# LTC6804-2_8S_TR.net
KiCad netlist of a schematic drawn in Altium Designer
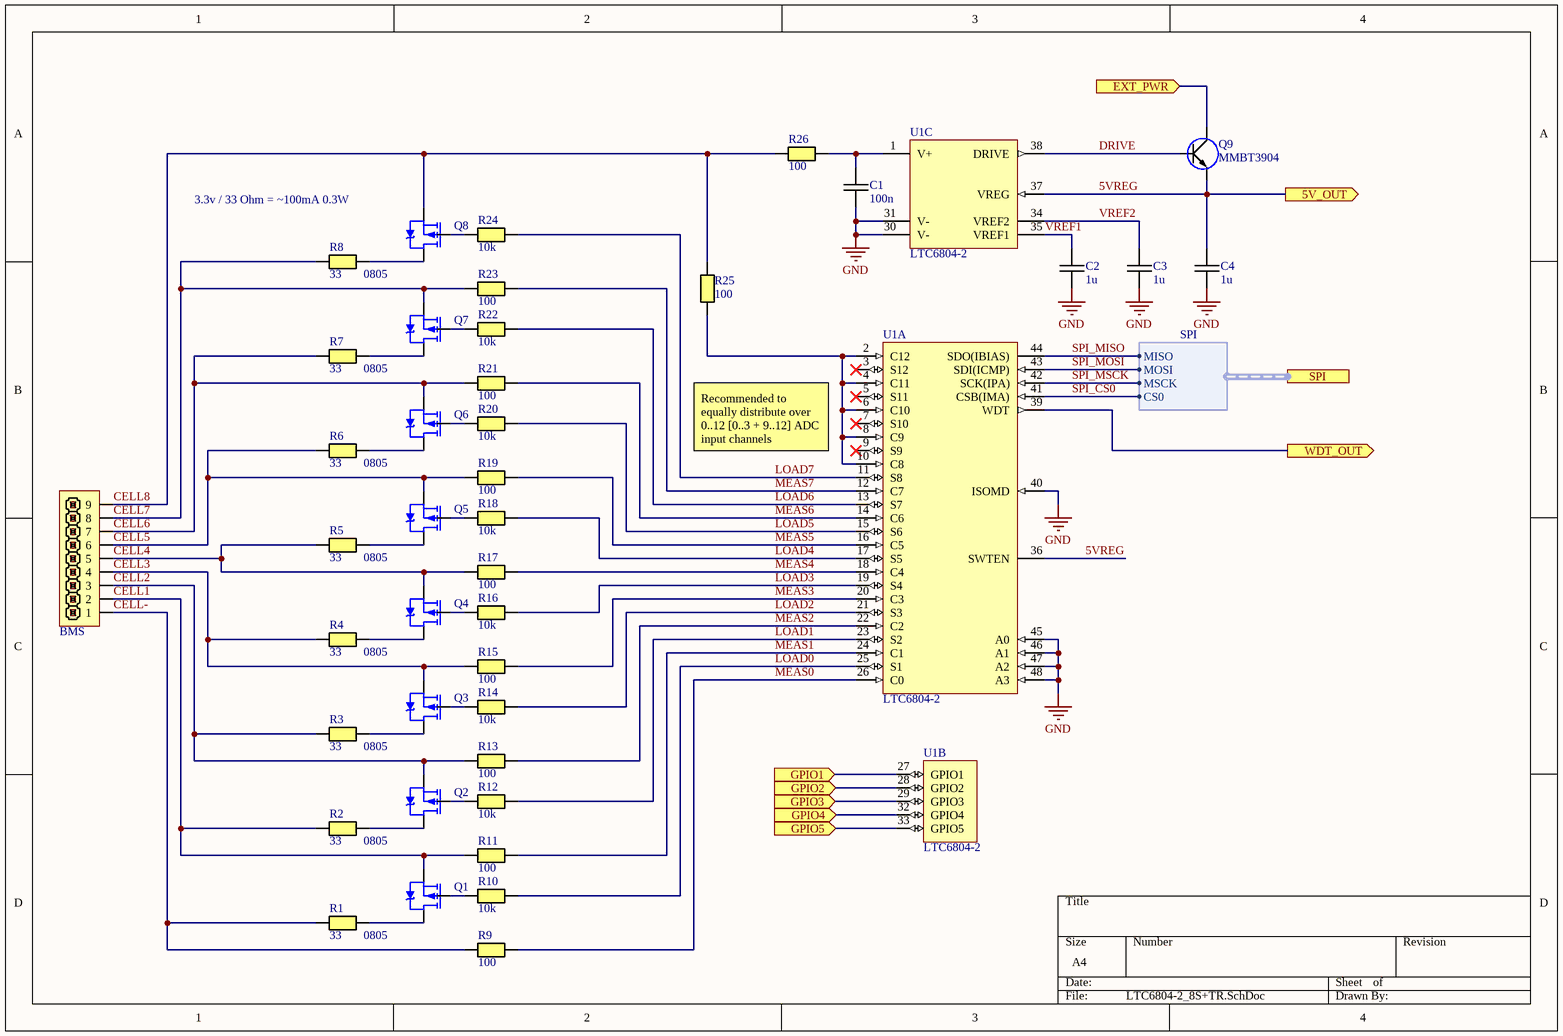
[diagram p0: LTC6804-2_8S+TR.SchDoc]

(export (version "E")
  (design (tool "Eeschema 10.0.6"))
  (components
    (comp (ref "BMS")
      (value "PIN HEADER 1x9")
      (footprint "XH2.54 9P")
      (libsource (lib "Connectors") (part "PIN HEADER 2.54 1x9"))
    )
    (comp (ref "C1")
      (value "100n")
      (footprint "CAPC0603(1608)55_N")
      (description "Ceramic capacitor Medium density")
      (libsource (lib "Discrete") (part "Capacitor M"))
    )
    (comp (ref "C2")
      (value "1u")
      (footprint "CAPC0805(2012)75_N")
      (description "Ceramic capacitor Medium density")
      (libsource (lib "Discrete") (part "Capacitor M"))
    )
    (comp (ref "C3")
      (value "1u")
      (footprint "CAPC0805(2012)75_N")
      (description "Ceramic capacitor Medium density")
      (libsource (lib "Discrete") (part "Capacitor M"))
    )
    (comp (ref "C4")
      (value "1u")
      (footprint "CAPC0805(2012)75_N")
      (description "Ceramic capacitor Medium density")
      (libsource (lib "Discrete") (part "Capacitor M"))
    )
    (comp (ref "Q1")
      (value "BSS308PE")
      (footprint "SOT23")
      (description "OptiMOS™ P3 Small-Signal-Transistor")
      (libsource (lib "Transistors") (part "BSS308PE"))
    )
    (comp (ref "Q2")
      (value "BSS308PE")
      (footprint "SOT23")
      (description "OptiMOS™ P3 Small-Signal-Transistor")
      (libsource (lib "Transistors") (part "BSS308PE"))
    )
    (comp (ref "Q3")
      (value "BSS308PE")
      (footprint "SOT23")
      (description "OptiMOS™ P3 Small-Signal-Transistor")
      (libsource (lib "Transistors") (part "BSS308PE"))
    )
    (comp (ref "Q4")
      (value "BSS308PE")
      (footprint "SOT23")
      (description "OptiMOS™ P3 Small-Signal-Transistor")
      (libsource (lib "Transistors") (part "BSS308PE"))
    )
    (comp (ref "Q5")
      (value "BSS308PE")
      (footprint "SOT23")
      (description "OptiMOS™ P3 Small-Signal-Transistor")
      (libsource (lib "Transistors") (part "BSS308PE"))
    )
    (comp (ref "Q6")
      (value "BSS308PE")
      (footprint "SOT23")
      (description "OptiMOS™ P3 Small-Signal-Transistor")
      (libsource (lib "Transistors") (part "BSS308PE"))
    )
    (comp (ref "Q7")
      (value "BSS308PE")
      (footprint "SOT23")
      (description "OptiMOS™ P3 Small-Signal-Transistor")
      (libsource (lib "Transistors") (part "BSS308PE"))
    )
    (comp (ref "Q8")
      (value "BSS308PE")
      (footprint "SOT23")
      (description "OptiMOS™ P3 Small-Signal-Transistor")
      (libsource (lib "Transistors") (part "BSS308PE"))
    )
    (comp (ref "Q9")
      (value "MMBT3904")
      (footprint "SOT23")
      (description "NPN General Purpose Transistor")
      (libsource (lib "Transistors") (part "2N3904"))
    )
    (comp (ref "R1")
      (value "33")
      (footprint "RESC0805(2012)_N")
      (description "Resistor Medium Density")
      (fields (field (name "PACK") "0805"))
      (libsource (lib "Discrete") (part "Resistor M"))
    )
    (comp (ref "R2")
      (value "33")
      (footprint "RESC0805(2012)_N")
      (description "Resistor Medium Density")
      (fields (field (name "PACK") "0805"))
      (libsource (lib "Discrete") (part "Resistor M"))
    )
    (comp (ref "R3")
      (value "33")
      (footprint "RESC0805(2012)_N")
      (description "Resistor Medium Density")
      (fields (field (name "PACK") "0805"))
      (libsource (lib "Discrete") (part "Resistor M"))
    )
    (comp (ref "R4")
      (value "33")
      (footprint "RESC0805(2012)_N")
      (description "Resistor Medium Density")
      (fields (field (name "PACK") "0805"))
      (libsource (lib "Discrete") (part "Resistor M"))
    )
    (comp (ref "R5")
      (value "33")
      (footprint "RESC0805(2012)_N")
      (description "Resistor Medium Density")
      (fields (field (name "PACK") "0805"))
      (libsource (lib "Discrete") (part "Resistor M"))
    )
    (comp (ref "R6")
      (value "33")
      (footprint "RESC0805(2012)_N")
      (description "Resistor Medium Density")
      (fields (field (name "PACK") "0805"))
      (libsource (lib "Discrete") (part "Resistor M"))
    )
    (comp (ref "R7")
      (value "33")
      (footprint "RESC0805(2012)_N")
      (description "Resistor Medium Density")
      (fields (field (name "PACK") "0805"))
      (libsource (lib "Discrete") (part "Resistor M"))
    )
    (comp (ref "R8")
      (value "33")
      (footprint "RESC0805(2012)_N")
      (description "Resistor Medium Density")
      (fields (field (name "PACK") "0805"))
      (libsource (lib "Discrete") (part "Resistor M"))
    )
    (comp (ref "R9")
      (value "100")
      (footprint "RESC0603(1608)_N")
      (description "Resistor Medium Density")
      (libsource (lib "") (part "Resistor M_1"))
    )
    (comp (ref "R10")
      (value "10k")
      (footprint "RESC0603(1608)_N")
      (description "Resistor Medium Density")
      (libsource (lib "Discrete") (part "Resistor M"))
    )
    (comp (ref "R11")
      (value "100")
      (footprint "RESC0603(1608)_N")
      (description "Resistor Medium Density")
      (libsource (lib "") (part "Resistor M_1"))
    )
    (comp (ref "R12")
      (value "10k")
      (footprint "RESC0603(1608)_N")
      (description "Resistor Medium Density")
      (libsource (lib "Discrete") (part "Resistor M"))
    )
    (comp (ref "R13")
      (value "100")
      (footprint "RESC0603(1608)_N")
      (description "Resistor Medium Density")
      (libsource (lib "") (part "Resistor M_1"))
    )
    (comp (ref "R14")
      (value "10k")
      (footprint "RESC0603(1608)_N")
      (description "Resistor Medium Density")
      (libsource (lib "Discrete") (part "Resistor M"))
    )
    (comp (ref "R15")
      (value "100")
      (footprint "RESC0603(1608)_N")
      (description "Resistor Medium Density")
      (libsource (lib "") (part "Resistor M_1"))
    )
    (comp (ref "R16")
      (value "10k")
      (footprint "RESC0603(1608)_N")
      (description "Resistor Medium Density")
      (libsource (lib "Discrete") (part "Resistor M"))
    )
    (comp (ref "R17")
      (value "100")
      (footprint "RESC0603(1608)_N")
      (description "Resistor Medium Density")
      (libsource (lib "") (part "Resistor M_1"))
    )
    (comp (ref "R18")
      (value "10k")
      (footprint "RESC0603(1608)_N")
      (description "Resistor Medium Density")
      (libsource (lib "Discrete") (part "Resistor M"))
    )
    (comp (ref "R19")
      (value "100")
      (footprint "RESC0603(1608)_N")
      (description "Resistor Medium Density")
      (libsource (lib "") (part "Resistor M_1"))
    )
    (comp (ref "R20")
      (value "10k")
      (footprint "RESC0603(1608)_N")
      (description "Resistor Medium Density")
      (libsource (lib "Discrete") (part "Resistor M"))
    )
    (comp (ref "R21")
      (value "100")
      (footprint "RESC0603(1608)_N")
      (description "Resistor Medium Density")
      (libsource (lib "") (part "Resistor M_1"))
    )
    (comp (ref "R22")
      (value "10k")
      (footprint "RESC0603(1608)_N")
      (description "Resistor Medium Density")
      (libsource (lib "Discrete") (part "Resistor M"))
    )
    (comp (ref "R23")
      (value "100")
      (footprint "RESC0603(1608)_N")
      (description "Resistor Medium Density")
      (libsource (lib "") (part "Resistor M_1"))
    )
    (comp (ref "R24")
      (value "10k")
      (footprint "RESC0603(1608)_N")
      (description "Resistor Medium Density")
      (libsource (lib "Discrete") (part "Resistor M"))
    )
    (comp (ref "R25")
      (value "100")
      (footprint "RESC0603(1608)_N")
      (description "Resistor Medium Density")
      (libsource (lib "") (part "Resistor M_2"))
    )
    (comp (ref "R26")
      (value "100")
      (footprint "RESC0603(1608)_N")
      (description "Resistor Medium Density")
      (libsource (lib "") (part "Resistor M_1"))
    )
    (comp (ref "U1") (value "LTC6804-2") (footprint "SSOP48") (libsource (lib "") (part "LTC6804-2_1")))
  )
  (nets
    (net (code "2") (name "/5VREG") (class "Default")
      (node (ref "C4") (pin "1") (pinfunction "1_1") (pintype "passive"))
      (node (ref "Q9") (pin "2") (pinfunction "E_2") (pintype "passive"))
      (node (ref "U1") (pin "36") (pinfunction "SWTEN_36") (pintype "passive"))
      (node (ref "U1") (pin "37") (pinfunction "VREG_37") (pintype "input"))
    )
    (net (code "3") (name "/CELL-") (class "Default")
      (node (ref "BMS") (pin "1") (pinfunction "1_1") (pintype "passive"))
      (node (ref "R1") (pin "1") (pinfunction "1_1") (pintype "passive"))
      (node (ref "R9") (pin "1") (pinfunction "1_1") (pintype "passive"))
    )
    (net (code "4") (name "/CELL1") (class "Default")
      (node (ref "BMS") (pin "2") (pinfunction "2_2") (pintype "passive"))
      (node (ref "Q1") (pin "2") (pinfunction "2_2") (pintype "passive"))
      (node (ref "R11") (pin "1") (pinfunction "1_1") (pintype "passive"))
      (node (ref "R2") (pin "1") (pinfunction "1_1") (pintype "passive"))
    )
    (net (code "5") (name "/CELL2") (class "Default")
      (node (ref "BMS") (pin "3") (pinfunction "3_3") (pintype "passive"))
      (node (ref "Q2") (pin "2") (pinfunction "2_2") (pintype "passive"))
      (node (ref "R13") (pin "1") (pinfunction "1_1") (pintype "passive"))
      (node (ref "R3") (pin "1") (pinfunction "1_1") (pintype "passive"))
    )
    (net (code "6") (name "/CELL3") (class "Default")
      (node (ref "BMS") (pin "4") (pinfunction "4_4") (pintype "passive"))
      (node (ref "Q3") (pin "2") (pinfunction "2_2") (pintype "passive"))
      (node (ref "R15") (pin "1") (pinfunction "1_1") (pintype "passive"))
      (node (ref "R4") (pin "1") (pinfunction "1_1") (pintype "passive"))
    )
    (net (code "7") (name "/CELL4") (class "Default")
      (node (ref "BMS") (pin "5") (pinfunction "5_5") (pintype "passive"))
      (node (ref "Q4") (pin "2") (pinfunction "2_2") (pintype "passive"))
      (node (ref "R17") (pin "1") (pinfunction "1_1") (pintype "passive"))
      (node (ref "R5") (pin "1") (pinfunction "1_1") (pintype "passive"))
    )
    (net (code "8") (name "/CELL5") (class "Default")
      (node (ref "BMS") (pin "6") (pinfunction "6_6") (pintype "passive"))
      (node (ref "Q5") (pin "2") (pinfunction "2_2") (pintype "passive"))
      (node (ref "R19") (pin "1") (pinfunction "1_1") (pintype "passive"))
      (node (ref "R6") (pin "1") (pinfunction "1_1") (pintype "passive"))
    )
    (net (code "9") (name "/CELL6") (class "Default")
      (node (ref "BMS") (pin "7") (pinfunction "7_7") (pintype "passive"))
      (node (ref "Q6") (pin "2") (pinfunction "2_2") (pintype "passive"))
      (node (ref "R21") (pin "1") (pinfunction "1_1") (pintype "passive"))
      (node (ref "R7") (pin "1") (pinfunction "1_1") (pintype "passive"))
    )
    (net (code "10") (name "/CELL7") (class "Default")
      (node (ref "BMS") (pin "8") (pinfunction "8_8") (pintype "passive"))
      (node (ref "Q7") (pin "2") (pinfunction "2_2") (pintype "passive"))
      (node (ref "R23") (pin "1") (pinfunction "1_1") (pintype "passive"))
      (node (ref "R8") (pin "1") (pinfunction "1_1") (pintype "passive"))
    )
    (net (code "11") (name "/CELL8") (class "Default")
      (node (ref "BMS") (pin "9") (pinfunction "9_9") (pintype "passive"))
      (node (ref "Q8") (pin "2") (pinfunction "2_2") (pintype "passive"))
      (node (ref "R25") (pin "1") (pinfunction "1_1") (pintype "passive"))
      (node (ref "R26") (pin "1") (pinfunction "1_1") (pintype "passive"))
    )
    (net (code "12") (name "/DRIVE") (class "Default")
      (node (ref "Q9") (pin "1") (pinfunction "B_1") (pintype "passive"))
      (node (ref "U1") (pin "38") (pinfunction "DRIVE_38") (pintype "output"))
    )
    (net (code "13") (name "/EXT_PWR") (class "Default")
      (node (ref "Q9") (pin "3") (pinfunction "C_3") (pintype "passive"))
    )
    (net (code "14") (name "/GPIO1") (class "Default")
      (node (ref "U1") (pin "27") (pinfunction "GPIO1_27") (pintype "bidirectional"))
    )
    (net (code "15") (name "/GPIO2") (class "Default")
      (node (ref "U1") (pin "28") (pinfunction "GPIO2_28") (pintype "bidirectional"))
    )
    (net (code "16") (name "/GPIO3") (class "Default")
      (node (ref "U1") (pin "29") (pinfunction "GPIO3_29") (pintype "bidirectional"))
    )
    (net (code "17") (name "/GPIO4") (class "Default")
      (node (ref "U1") (pin "32") (pinfunction "GPIO4_32") (pintype "bidirectional"))
    )
    (net (code "18") (name "/GPIO5") (class "Default")
      (node (ref "U1") (pin "33") (pinfunction "GPIO5_33") (pintype "bidirectional"))
    )
    (net (code "19") (name "/LOAD0") (class "Default")
      (node (ref "R10") (pin "2") (pinfunction "2_2") (pintype "passive"))
      (node (ref "U1") (pin "25") (pinfunction "S1_25") (pintype "bidirectional"))
    )
    (net (code "20") (name "/LOAD1") (class "Default")
      (node (ref "R12") (pin "2") (pinfunction "2_2") (pintype "passive"))
      (node (ref "U1") (pin "23") (pinfunction "S2_23") (pintype "bidirectional"))
    )
    (net (code "21") (name "/LOAD2") (class "Default")
      (node (ref "R14") (pin "2") (pinfunction "2_2") (pintype "passive"))
      (node (ref "U1") (pin "21") (pinfunction "S3_21") (pintype "bidirectional"))
    )
    (net (code "22") (name "/LOAD3") (class "Default")
      (node (ref "R16") (pin "2") (pinfunction "2_2") (pintype "passive"))
      (node (ref "U1") (pin "19") (pinfunction "S4_19") (pintype "bidirectional"))
    )
    (net (code "23") (name "/LOAD4") (class "Default")
      (node (ref "R18") (pin "2") (pinfunction "2_2") (pintype "passive"))
      (node (ref "U1") (pin "17") (pinfunction "S5_17") (pintype "bidirectional"))
    )
    (net (code "24") (name "/LOAD5") (class "Default")
      (node (ref "R20") (pin "2") (pinfunction "2_2") (pintype "passive"))
      (node (ref "U1") (pin "15") (pinfunction "S6_15") (pintype "bidirectional"))
    )
    (net (code "25") (name "/LOAD6") (class "Default")
      (node (ref "R22") (pin "2") (pinfunction "2_2") (pintype "passive"))
      (node (ref "U1") (pin "13") (pinfunction "S7_13") (pintype "bidirectional"))
    )
    (net (code "26") (name "/LOAD7") (class "Default")
      (node (ref "R24") (pin "2") (pinfunction "2_2") (pintype "passive"))
      (node (ref "U1") (pin "11") (pinfunction "S8_11") (pintype "bidirectional"))
    )
    (net (code "27") (name "/MEAS0") (class "Default")
      (node (ref "R9") (pin "2") (pinfunction "2_2") (pintype "passive"))
      (node (ref "U1") (pin "26") (pinfunction "C0_26") (pintype "input"))
    )
    (net (code "28") (name "/MEAS1") (class "Default")
      (node (ref "R11") (pin "2") (pinfunction "2_2") (pintype "passive"))
      (node (ref "U1") (pin "24") (pinfunction "C1_24") (pintype "input"))
    )
    (net (code "29") (name "/MEAS2") (class "Default")
      (node (ref "R13") (pin "2") (pinfunction "2_2") (pintype "passive"))
      (node (ref "U1") (pin "22") (pinfunction "C2_22") (pintype "input"))
    )
    (net (code "30") (name "/MEAS3") (class "Default")
      (node (ref "R15") (pin "2") (pinfunction "2_2") (pintype "passive"))
      (node (ref "U1") (pin "20") (pinfunction "C3_20") (pintype "input"))
    )
    (net (code "31") (name "/MEAS4") (class "Default")
      (node (ref "R17") (pin "2") (pinfunction "2_2") (pintype "passive"))
      (node (ref "U1") (pin "18") (pinfunction "C4_18") (pintype "input"))
    )
    (net (code "32") (name "/MEAS5") (class "Default")
      (node (ref "R19") (pin "2") (pinfunction "2_2") (pintype "passive"))
      (node (ref "U1") (pin "16") (pinfunction "C5_16") (pintype "input"))
    )
    (net (code "33") (name "/MEAS6") (class "Default")
      (node (ref "R21") (pin "2") (pinfunction "2_2") (pintype "passive"))
      (node (ref "U1") (pin "14") (pinfunction "C6_14") (pintype "input"))
    )
    (net (code "34") (name "/MEAS7") (class "Default")
      (node (ref "R23") (pin "2") (pinfunction "2_2") (pintype "passive"))
      (node (ref "U1") (pin "12") (pinfunction "C7_12") (pintype "input"))
    )
    (net (code "35") (name "/SPI_CS0") (class "Default")
      (node (ref "U1") (pin "41") (pinfunction "CSB(IMA)_41") (pintype "input"))
    )
    (net (code "36") (name "/SPI_MISO") (class "Default")
      (node (ref "U1") (pin "44") (pinfunction "SDO(IBIAS)_44") (pintype "open_collector"))
    )
    (net (code "37") (name "/SPI_MOSI") (class "Default")
      (node (ref "U1") (pin "43") (pinfunction "SDI(ICMP)_43") (pintype "input"))
    )
    (net (code "38") (name "/SPI_MSCK") (class "Default")
      (node (ref "U1") (pin "42") (pinfunction "SCK(IPA)_42") (pintype "input"))
    )
    (net (code "39") (name "/VREF1") (class "Default")
      (node (ref "C2") (pin "1") (pinfunction "1_1") (pintype "passive"))
      (node (ref "U1") (pin "35") (pinfunction "VREF1_35") (pintype "power_in"))
    )
    (net (code "40") (name "/VREF2") (class "Default")
      (node (ref "C3") (pin "1") (pinfunction "1_1") (pintype "passive"))
      (node (ref "U1") (pin "34") (pinfunction "VREF2_34") (pintype "power_in"))
    )
    (net (code "41") (name "/WDT_OUT") (class "Default")
      (node (ref "U1") (pin "39") (pinfunction "WDT_39") (pintype "output"))
    )
    (net (code "43") (name "GND") (class "Default")
      (node (ref "C1") (pin "2") (pinfunction "2_2") (pintype "passive"))
      (node (ref "C2") (pin "2") (pinfunction "2_2") (pintype "passive"))
      (node (ref "C3") (pin "2") (pinfunction "2_2") (pintype "passive"))
      (node (ref "C4") (pin "2") (pinfunction "2_2") (pintype "passive"))
      (node (ref "U1") (pin "30") (pinfunction "V-_30") (pintype "power_in"))
      (node (ref "U1") (pin "31") (pinfunction "V-_31") (pintype "power_in"))
      (node (ref "U1") (pin "40") (pinfunction "ISOMD_40") (pintype "input"))
      (node (ref "U1") (pin "45") (pinfunction "A0_45") (pintype "input"))
      (node (ref "U1") (pin "46") (pinfunction "A1_46") (pintype "input"))
      (node (ref "U1") (pin "47") (pinfunction "A2_47") (pintype "input"))
      (node (ref "U1") (pin "48") (pinfunction "A3_48") (pintype "input"))
    )
    (net (code "44") (name "Net-(Q1-Pad1)") (class "Default")
      (node (ref "Q1") (pin "1") (pinfunction "1_1") (pintype "passive"))
      (node (ref "R10") (pin "1") (pinfunction "1_1") (pintype "passive"))
    )
    (net (code "45") (name "Net-(Q1-Pad3)") (class "Default")
      (node (ref "Q1") (pin "3") (pinfunction "3_3") (pintype "passive"))
      (node (ref "R1") (pin "2") (pinfunction "2_2") (pintype "passive"))
    )
    (net (code "46") (name "Net-(Q2-Pad1)") (class "Default")
      (node (ref "Q2") (pin "1") (pinfunction "1_1") (pintype "passive"))
      (node (ref "R12") (pin "1") (pinfunction "1_1") (pintype "passive"))
    )
    (net (code "47") (name "Net-(Q2-Pad3)") (class "Default")
      (node (ref "Q2") (pin "3") (pinfunction "3_3") (pintype "passive"))
      (node (ref "R2") (pin "2") (pinfunction "2_2") (pintype "passive"))
    )
    (net (code "48") (name "Net-(Q3-Pad1)") (class "Default")
      (node (ref "Q3") (pin "1") (pinfunction "1_1") (pintype "passive"))
      (node (ref "R14") (pin "1") (pinfunction "1_1") (pintype "passive"))
    )
    (net (code "49") (name "Net-(Q3-Pad3)") (class "Default")
      (node (ref "Q3") (pin "3") (pinfunction "3_3") (pintype "passive"))
      (node (ref "R3") (pin "2") (pinfunction "2_2") (pintype "passive"))
    )
    (net (code "50") (name "Net-(Q4-Pad1)") (class "Default")
      (node (ref "Q4") (pin "1") (pinfunction "1_1") (pintype "passive"))
      (node (ref "R16") (pin "1") (pinfunction "1_1") (pintype "passive"))
    )
    (net (code "51") (name "Net-(Q4-Pad3)") (class "Default")
      (node (ref "Q4") (pin "3") (pinfunction "3_3") (pintype "passive"))
      (node (ref "R4") (pin "2") (pinfunction "2_2") (pintype "passive"))
    )
    (net (code "52") (name "Net-(Q5-Pad1)") (class "Default")
      (node (ref "Q5") (pin "1") (pinfunction "1_1") (pintype "passive"))
      (node (ref "R18") (pin "1") (pinfunction "1_1") (pintype "passive"))
    )
    (net (code "53") (name "Net-(Q5-Pad3)") (class "Default")
      (node (ref "Q5") (pin "3") (pinfunction "3_3") (pintype "passive"))
      (node (ref "R5") (pin "2") (pinfunction "2_2") (pintype "passive"))
    )
    (net (code "54") (name "Net-(Q6-Pad1)") (class "Default")
      (node (ref "Q6") (pin "1") (pinfunction "1_1") (pintype "passive"))
      (node (ref "R20") (pin "1") (pinfunction "1_1") (pintype "passive"))
    )
    (net (code "55") (name "Net-(Q6-Pad3)") (class "Default")
      (node (ref "Q6") (pin "3") (pinfunction "3_3") (pintype "passive"))
      (node (ref "R6") (pin "2") (pinfunction "2_2") (pintype "passive"))
    )
    (net (code "56") (name "Net-(Q7-Pad1)") (class "Default")
      (node (ref "Q7") (pin "1") (pinfunction "1_1") (pintype "passive"))
      (node (ref "R22") (pin "1") (pinfunction "1_1") (pintype "passive"))
    )
    (net (code "57") (name "Net-(Q7-Pad3)") (class "Default")
      (node (ref "Q7") (pin "3") (pinfunction "3_3") (pintype "passive"))
      (node (ref "R7") (pin "2") (pinfunction "2_2") (pintype "passive"))
    )
    (net (code "58") (name "Net-(Q8-Pad1)") (class "Default")
      (node (ref "Q8") (pin "1") (pinfunction "1_1") (pintype "passive"))
      (node (ref "R24") (pin "1") (pinfunction "1_1") (pintype "passive"))
    )
    (net (code "59") (name "Net-(Q8-Pad3)") (class "Default")
      (node (ref "Q8") (pin "3") (pinfunction "3_3") (pintype "passive"))
      (node (ref "R8") (pin "2") (pinfunction "2_2") (pintype "passive"))
    )
    (net (code "60") (name "Net-(U1A-C10)") (class "Default")
      (node (ref "R25") (pin "2") (pinfunction "2_2") (pintype "passive"))
      (node (ref "U1") (pin "10") (pinfunction "C8_10") (pintype "input"))
      (node (ref "U1") (pin "2") (pinfunction "C12_2") (pintype "input"))
      (node (ref "U1") (pin "4") (pinfunction "C11_4") (pintype "input"))
      (node (ref "U1") (pin "6") (pinfunction "C10_6") (pintype "input"))
      (node (ref "U1") (pin "8") (pinfunction "C9_8") (pintype "input"))
    )
    (net (code "61") (name "Net-(U1C-V+)") (class "Default")
      (node (ref "C1") (pin "1") (pinfunction "1_1") (pintype "passive"))
      (node (ref "R26") (pin "2") (pinfunction "2_2") (pintype "passive"))
      (node (ref "U1") (pin "1") (pinfunction "V+_1") (pintype "power_in"))
    )
    (net (code "62") (name "unconnected-(U1A-S9-Pad9)") (class "Default")
      (node (ref "U1") (pin "9") (pinfunction "S9_9") (pintype "bidirectional+no_connect"))
    )
    (net (code "63") (name "unconnected-(U1A-S10-Pad7)") (class "Default")
      (node (ref "U1") (pin "7") (pinfunction "S10_7") (pintype "bidirectional+no_connect"))
    )
    (net (code "64") (name "unconnected-(U1A-S11-Pad5)") (class "Default")
      (node (ref "U1") (pin "5") (pinfunction "S11_5") (pintype "bidirectional+no_connect"))
    )
    (net (code "65") (name "unconnected-(U1A-S12-Pad3)") (class "Default")
      (node (ref "U1") (pin "3") (pinfunction "S12_3") (pintype "bidirectional+no_connect"))
    )
  )
)
